# pcb.net
KiCad netlist of a schematic drawn in EAGLE
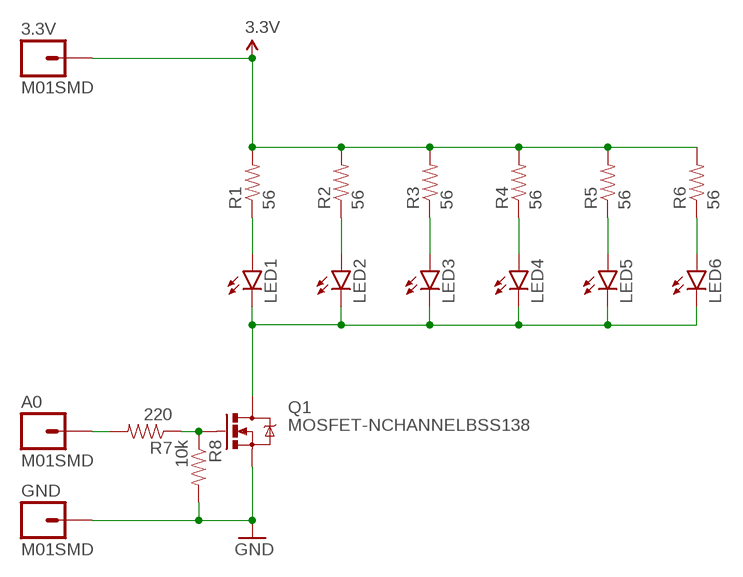
[diagram p0: schematic, sheet 1]

(export (version "E")
  (design (tool "Eeschema 10.0.6"))
  (components
    (comp (ref "3.3V")
      (value "M01SMD")
      (footprint "eagle-import:LUXEON-PAD")
      (libsource (lib "eagle-import") (part "M01SMD"))
    )
    (comp (ref "A0")
      (value "M01SMD")
      (footprint "eagle-import:LUXEON-PAD")
      (libsource (lib "eagle-import") (part "M01SMD"))
    )
    (comp (ref "GND")
      (value "M01SMD")
      (footprint "eagle-import:LUXEON-PAD")
      (libsource (lib "eagle-import") (part "M01SMD"))
    )
    (comp (ref "LED1")
      (value "LED1206")
      (footprint "eagle-import:LED-1206")
      (libsource (lib "eagle-import") (part "LED1206"))
    )
    (comp (ref "LED2")
      (value "LED1206")
      (footprint "eagle-import:LED-1206")
      (libsource (lib "eagle-import") (part "LED1206"))
    )
    (comp (ref "LED3")
      (value "LED1206")
      (footprint "eagle-import:LED-1206")
      (libsource (lib "eagle-import") (part "LED1206"))
    )
    (comp (ref "LED4")
      (value "LED1206")
      (footprint "eagle-import:LED-1206")
      (libsource (lib "eagle-import") (part "LED1206"))
    )
    (comp (ref "LED5")
      (value "LED1206")
      (footprint "eagle-import:LED-1206")
      (libsource (lib "eagle-import") (part "LED1206"))
    )
    (comp (ref "LED6")
      (value "LED1206")
      (footprint "eagle-import:LED-1206")
      (libsource (lib "eagle-import") (part "LED1206"))
    )
    (comp (ref "Q1")
      (value "MOSFET-NCHANNELBSS138")
      (footprint "eagle-import:SOT23-3")
      (libsource (lib "eagle-import") (part "MOSFET-NCHANNELBSS138"))
    )
    (comp (ref "R1")
      (value "56")
      (footprint "eagle-import:0603-RES")
      (libsource (lib "eagle-import") (part "RESISTOR0603"))
    )
    (comp (ref "R2")
      (value "56")
      (footprint "eagle-import:0603-RES")
      (libsource (lib "eagle-import") (part "RESISTOR0603"))
    )
    (comp (ref "R3")
      (value "56")
      (footprint "eagle-import:0603-RES")
      (libsource (lib "eagle-import") (part "RESISTOR0603"))
    )
    (comp (ref "R4")
      (value "56")
      (footprint "eagle-import:0603-RES")
      (libsource (lib "eagle-import") (part "RESISTOR0603"))
    )
    (comp (ref "R5")
      (value "56")
      (footprint "eagle-import:0603-RES")
      (libsource (lib "eagle-import") (part "RESISTOR0603"))
    )
    (comp (ref "R6")
      (value "56")
      (footprint "eagle-import:0603-RES")
      (libsource (lib "eagle-import") (part "RESISTOR0603"))
    )
    (comp (ref "R7")
      (value "220")
      (footprint "eagle-import:0603-RES")
      (libsource (lib "eagle-import") (part "RESISTOR0603"))
    )
    (comp (ref "R8")
      (value "10k")
      (footprint "eagle-import:0603-RES")
      (libsource (lib "eagle-import") (part "RESISTOR0603"))
    )
  )
  (nets
    (net (code "1") (name "3.3V") (class "Default")
      (node (ref "3.3V") (pin "P$1") (pinfunction "1_P$1") (pintype "passive"))
      (node (ref "R1") (pin "2") (pinfunction "2_2") (pintype "passive"))
      (node (ref "R2") (pin "2") (pinfunction "2_2") (pintype "passive"))
      (node (ref "R3") (pin "2") (pinfunction "2_2") (pintype "passive"))
      (node (ref "R4") (pin "2") (pinfunction "2_2") (pintype "passive"))
      (node (ref "R5") (pin "2") (pinfunction "2_2") (pintype "passive"))
      (node (ref "R6") (pin "2") (pinfunction "2_2") (pintype "passive"))
    )
    (net (code "2") (name "GND") (class "Default")
      (node (ref "GND") (pin "P$1") (pinfunction "1_P$1") (pintype "passive"))
      (node (ref "Q1") (pin "2") (pinfunction "S_2") (pintype "passive"))
      (node (ref "R8") (pin "2") (pinfunction "2_2") (pintype "passive"))
    )
    (net (code "3") (name "Net-(A0-1)") (class "Default")
      (node (ref "A0") (pin "P$1") (pinfunction "1_P$1") (pintype "passive"))
      (node (ref "R7") (pin "2") (pinfunction "2_2") (pintype "passive"))
    )
    (net (code "4") (name "Net-(LED1-PadA)") (class "Default")
      (node (ref "LED1") (pin "A") (pinfunction "A_A") (pintype "passive"))
      (node (ref "R1") (pin "1") (pinfunction "1_1") (pintype "passive"))
    )
    (net (code "5") (name "Net-(LED2-PadA)") (class "Default")
      (node (ref "LED2") (pin "A") (pinfunction "A_A") (pintype "passive"))
      (node (ref "R2") (pin "1") (pinfunction "1_1") (pintype "passive"))
    )
    (net (code "6") (name "Net-(LED3-PadA)") (class "Default")
      (node (ref "LED3") (pin "A") (pinfunction "A_A") (pintype "passive"))
      (node (ref "R3") (pin "1") (pinfunction "1_1") (pintype "passive"))
    )
    (net (code "7") (name "Net-(LED4-PadA)") (class "Default")
      (node (ref "LED4") (pin "A") (pinfunction "A_A") (pintype "passive"))
      (node (ref "R4") (pin "1") (pinfunction "1_1") (pintype "passive"))
    )
    (net (code "8") (name "Net-(LED5-PadA)") (class "Default")
      (node (ref "LED5") (pin "A") (pinfunction "A_A") (pintype "passive"))
      (node (ref "R5") (pin "1") (pinfunction "1_1") (pintype "passive"))
    )
    (net (code "9") (name "Net-(LED6-PadA)") (class "Default")
      (node (ref "LED6") (pin "A") (pinfunction "A_A") (pintype "passive"))
      (node (ref "R6") (pin "1") (pinfunction "1_1") (pintype "passive"))
    )
    (net (code "10") (name "Net-(Q1-D)") (class "Default")
      (node (ref "LED1") (pin "C") (pinfunction "C_C") (pintype "passive"))
      (node (ref "LED2") (pin "C") (pinfunction "C_C") (pintype "passive"))
      (node (ref "LED3") (pin "C") (pinfunction "C_C") (pintype "passive"))
      (node (ref "LED4") (pin "C") (pinfunction "C_C") (pintype "passive"))
      (node (ref "LED5") (pin "C") (pinfunction "C_C") (pintype "passive"))
      (node (ref "LED6") (pin "C") (pinfunction "C_C") (pintype "passive"))
      (node (ref "Q1") (pin "3") (pinfunction "D_3") (pintype "passive"))
    )
    (net (code "11") (name "Net-(Q1-G)") (class "Default")
      (node (ref "Q1") (pin "1") (pinfunction "G_1") (pintype "passive"))
      (node (ref "R7") (pin "1") (pinfunction "1_1") (pintype "passive"))
      (node (ref "R8") (pin "1") (pinfunction "1_1") (pintype "passive"))
    )
  )
)
